# DCC_Signal_Input.net
KiCad netlist of a schematic drawn in EasyEDA
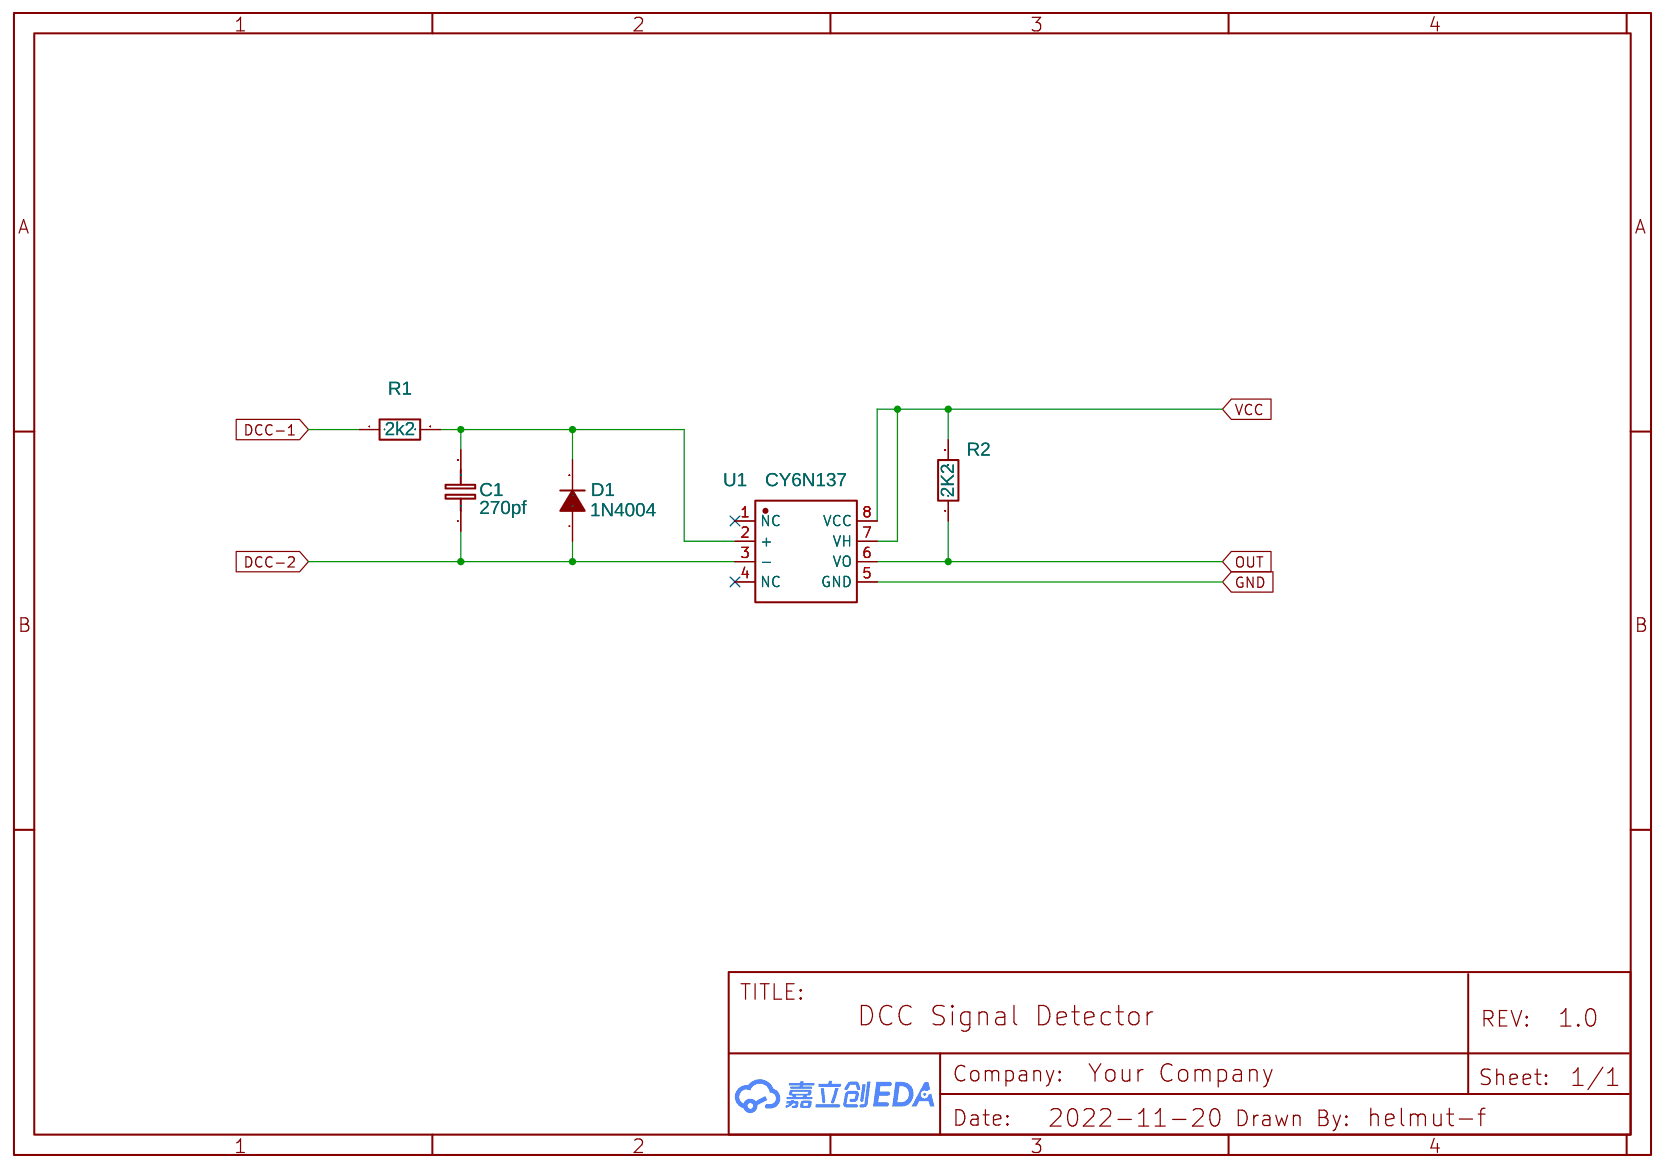
[diagram p0: schematic sheet]

(export (version "E")
  (design (tool "Eeschema 10.0.6"))
  (components
    (comp (ref "C1") (value "270pf") (libsource (lib "") (part "C_RAD-0.2_EU")))
    (comp (ref "D1")
      (value "1N4004")
      (fields (field (name "BOM_Supplier Part") "C3058"))
      (libsource (lib "") (part "1N4004"))
    )
    (comp (ref "R1") (value "2k2") (libsource (lib "") (part "R_AXIAL-0.3_EU")))
    (comp (ref "R2") (value "2K2") (libsource (lib "") (part "R_AXIAL-0.3_EU_1")))
    (comp (ref "U1")
      (value "CY6N137")
      (fields (field (name "BOM_Supplier Part") "C970352"))
      (libsource (lib "") (part "CY6N137"))
    )
  )
  (nets
    (net (code "1") (name "DCC-1") (class "Default")
      (node (ref "R1") (pin "1") (pinfunction "1_1") (pintype "unspecified"))
    )
    (net (code "2") (name "DCC-2") (class "Default")
      (node (ref "C1") (pin "1") (pinfunction "1_1") (pintype "unspecified"))
      (node (ref "D1") (pin "1") (pinfunction "A_1") (pintype "unspecified"))
      (node (ref "U1") (pin "3") (pinfunction "-_3") (pintype "unspecified"))
    )
    (net (code "3") (name "GND") (class "Default")
      (node (ref "U1") (pin "5") (pinfunction "GND_5") (pintype "unspecified"))
    )
    (net (code "4") (name "Net-(D1-K)") (class "Default")
      (node (ref "C1") (pin "2") (pinfunction "2_2") (pintype "unspecified"))
      (node (ref "D1") (pin "2") (pinfunction "K_2") (pintype "unspecified"))
      (node (ref "R1") (pin "2") (pinfunction "2_2") (pintype "unspecified"))
      (node (ref "U1") (pin "2") (pinfunction "+_2") (pintype "unspecified"))
    )
    (net (code "5") (name "OUT") (class "Default")
      (node (ref "R2") (pin "1") (pinfunction "1_1") (pintype "unspecified"))
      (node (ref "U1") (pin "6") (pinfunction "VO_6") (pintype "unspecified"))
    )
    (net (code "6") (name "VCC") (class "Default")
      (node (ref "R2") (pin "2") (pinfunction "2_2") (pintype "unspecified"))
      (node (ref "U1") (pin "7") (pinfunction "VH_7") (pintype "unspecified"))
      (node (ref "U1") (pin "8") (pinfunction "VCC_8") (pintype "unspecified"))
    )
    (net (code "7") (name "unconnected-(U1-NC-Pad1)") (class "Default")
      (node (ref "U1") (pin "1") (pinfunction "NC_1") (pintype "unspecified+no_connect"))
    )
    (net (code "8") (name "unconnected-(U1-NC-Pad4)") (class "Default")
      (node (ref "U1") (pin "4") (pinfunction "NC_4") (pintype "unspecified+no_connect"))
    )
  )
)
